# EEZ_DIB_BP3C_r2B1.net
KiCad netlist of a schematic drawn in EAGLE
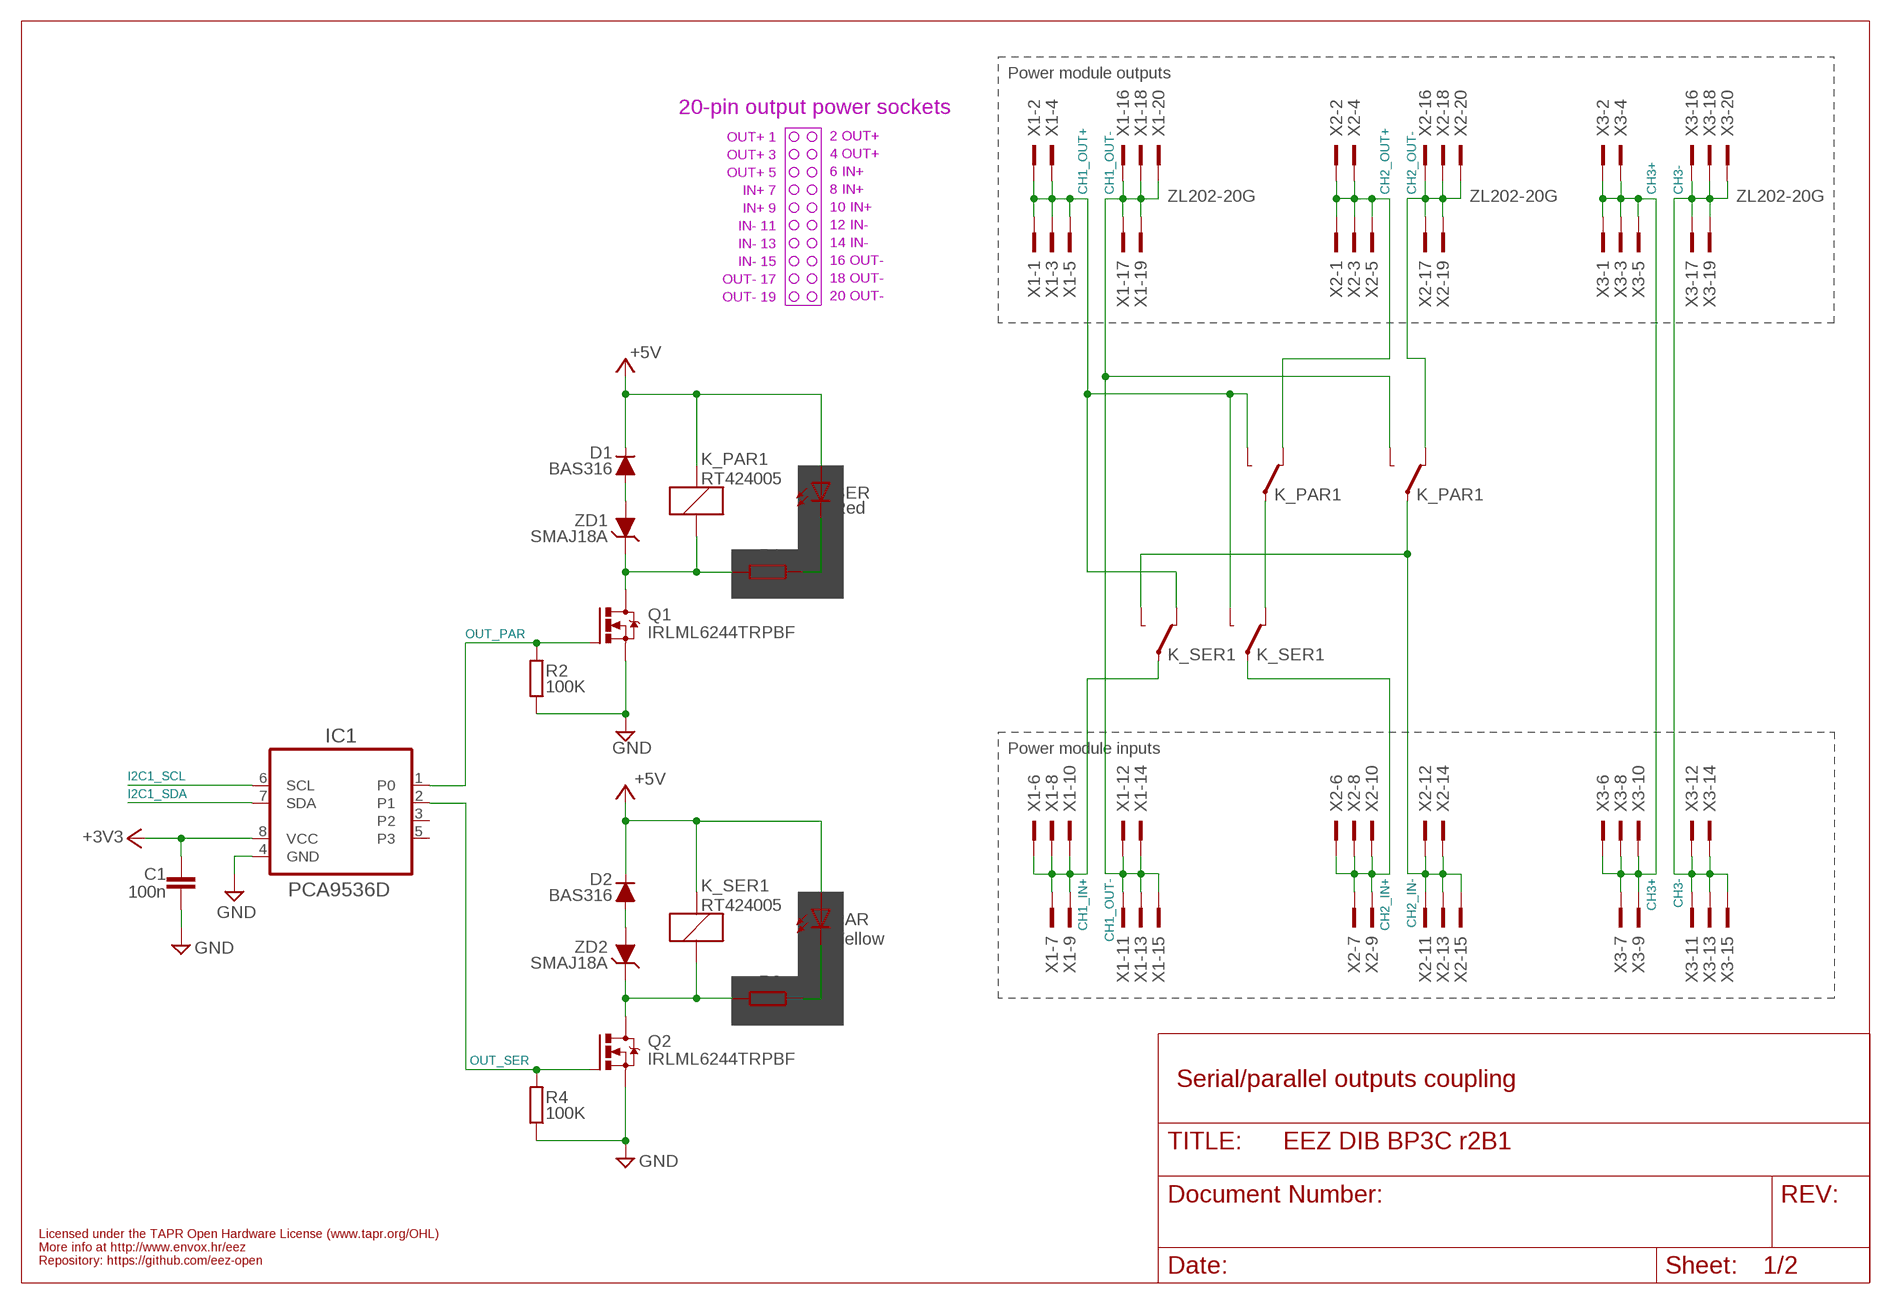
[diagram p0: schematic, sheet 1]
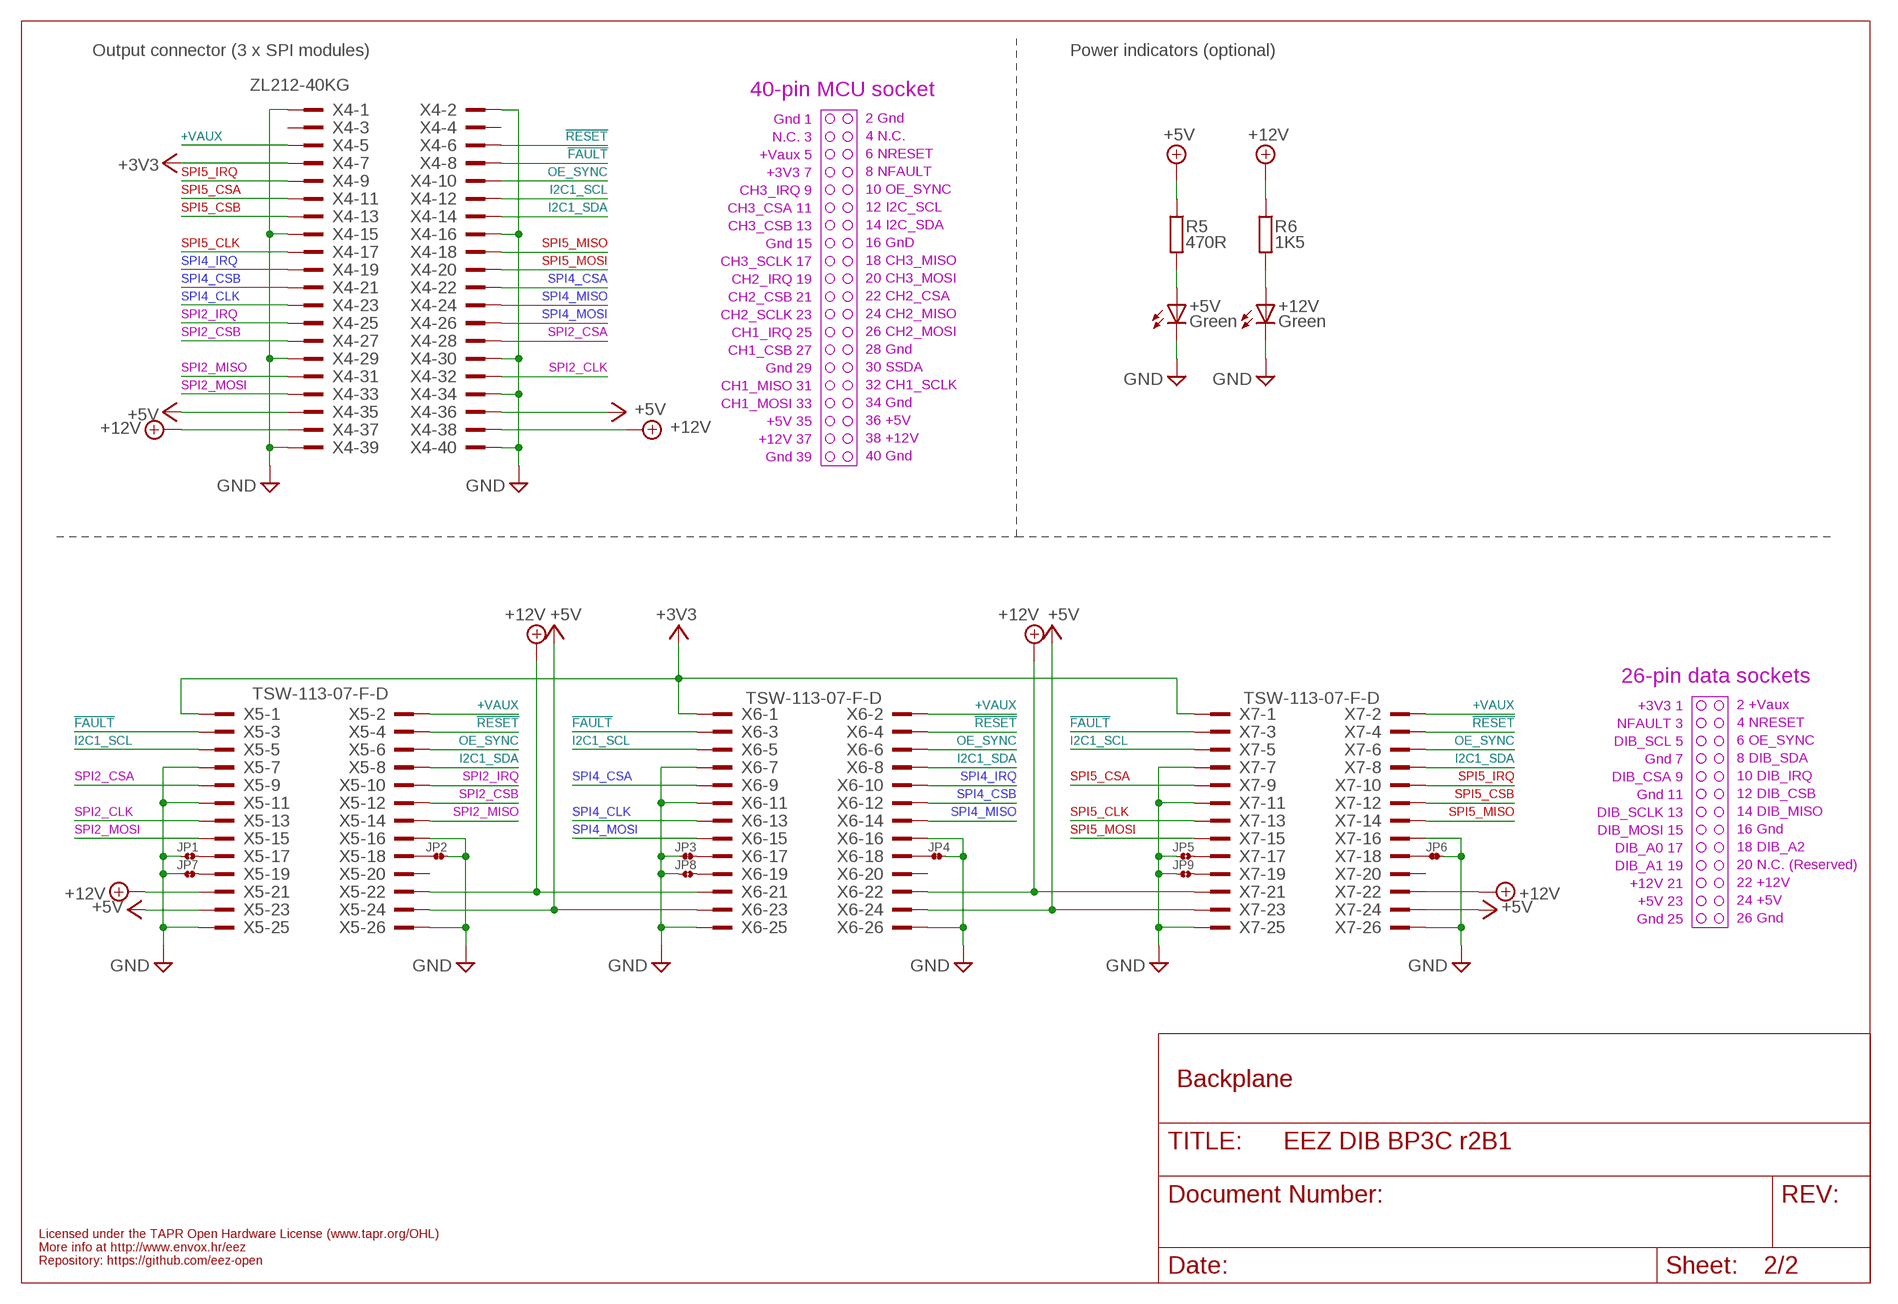
[diagram p1: schematic, sheet 2]

(export (version "E")
  (design (tool "Eeschema 10.0.6"))
  (components
    (comp (ref "C1")
      (value "100n")
      (footprint "eagle-import:C0603")
      (libsource (lib "eagle-import") (part "C-EUC0603"))
    )
    (comp (ref "D1")
      (value "BAS316")
      (footprint "eagle-import:SOD323-R")
      (libsource (lib "eagle-import") (part "DIODESOD323R"))
    )
    (comp (ref "D2")
      (value "BAS316")
      (footprint "eagle-import:SOD323-R")
      (libsource (lib "eagle-import") (part "DIODESOD323R"))
    )
    (comp (ref "IC1")
      (value "PCA9536D")
      (footprint "eagle-import:SOIC127P600X173-8N")
      (libsource (lib "eagle-import") (part "PCA9536D"))
    )
    (comp (ref "K_PAR1")
      (value "RT424005")
      (footprint "eagle-import:RT-C_016A5_ROUND")
      (libsource (lib "eagle-import") (part "RELAY_RT314012-2"))
    )
    (comp (ref "K_SER1")
      (value "RT424005")
      (footprint "eagle-import:RT-C_016A5_ROUND")
      (libsource (lib "eagle-import") (part "RELAY_RT314012-2"))
    )
    (comp (ref "PAR")
      (value "Yellow")
      (footprint "eagle-import:LED_0805")
      (libsource (lib "eagle-import") (part "LED0805"))
    )
    (comp (ref "Q1")
      (value "IRLML6244TRPBF")
      (footprint "eagle-import:SOT103P240X110-3N")
      (fields
        (field (name "MPN") "2N7002-7-F")
        (field (name "MPN_1") "2N7002-7-F")
        (field (name "OC_FARNELL") "1713823")
        (field (name "OC_NEWARK") "25R5679")
        (field (name "PACKAGE") "SOT-23-3")
        (field (name "SUPPLIER") "DIODES INC.")
      )
      (libsource (lib "eagle-import") (part "2N7002"))
    )
    (comp (ref "Q2")
      (value "IRLML6244TRPBF")
      (footprint "eagle-import:SOT103P240X110-3N")
      (fields
        (field (name "MPN") "2N7002-7-F")
        (field (name "MPN_1") "2N7002-7-F")
        (field (name "OC_FARNELL") "1713823")
        (field (name "OC_NEWARK") "25R5679")
        (field (name "PACKAGE") "SOT-23-3")
        (field (name "SUPPLIER") "DIODES INC.")
      )
      (libsource (lib "eagle-import") (part "2N7002"))
    )
    (comp (ref "R1")
      (value "330R")
      (footprint "eagle-import:R0805")
      (libsource (lib "eagle-import") (part "R-EU_R0805"))
    )
    (comp (ref "R2")
      (value "100K")
      (footprint "eagle-import:R0805")
      (libsource (lib "eagle-import") (part "R-EU_R0805"))
    )
    (comp (ref "R3")
      (value "330R")
      (footprint "eagle-import:R0805")
      (libsource (lib "eagle-import") (part "R-EU_R0805"))
    )
    (comp (ref "R4")
      (value "100K")
      (footprint "eagle-import:R0805")
      (libsource (lib "eagle-import") (part "R-EU_R0805"))
    )
    (comp (ref "SER")
      (value "Red")
      (footprint "eagle-import:LED_0805")
      (libsource (lib "eagle-import") (part "LED0805"))
    )
    (comp (ref "X1")
      (value "ZL202-20G")
      (footprint "eagle-import:DS1021-2_10SF11")
      (libsource (lib "eagle-import") (part "DS1021-210SF11"))
    )
    (comp (ref "X2")
      (value "ZL202-20G")
      (footprint "eagle-import:DS1021-2_10SF11")
      (libsource (lib "eagle-import") (part "DS1021-210SF11"))
    )
    (comp (ref "X3")
      (value "ZL202-20G")
      (footprint "eagle-import:DS1021-2_10SF11")
      (libsource (lib "eagle-import") (part "DS1021-210SF11"))
    )
    (comp (ref "ZD1")
      (value "SMAJ18A")
      (footprint "eagle-import:DO214AC")
      (libsource (lib "eagle-import") (part "PSMAXX"))
    )
    (comp (ref "ZD2")
      (value "SMAJ18A")
      (footprint "eagle-import:DO214AC")
      (libsource (lib "eagle-import") (part "PSMAXX"))
    )
    (comp (ref "+5V")
      (value "Green")
      (footprint "eagle-import:LED_0805")
      (libsource (lib "eagle-import") (part "LED0805"))
    )
    (comp (ref "+12V")
      (value "Green")
      (footprint "eagle-import:LED_0805")
      (libsource (lib "eagle-import") (part "LED0805"))
    )
    (comp (ref "JP1")
      (value "JP2-CUT")
      (footprint "eagle-import:JP2-CUT")
      (libsource (lib "eagle-import") (part "JP2-CUT"))
    )
    (comp (ref "JP2")
      (value "JP2-NOCUT")
      (footprint "eagle-import:JP2-NOCUT")
      (libsource (lib "eagle-import") (part "JP2-NOCUT"))
    )
    (comp (ref "JP3")
      (value "JP2-NOCUT")
      (footprint "eagle-import:JP2-NOCUT")
      (libsource (lib "eagle-import") (part "JP2-NOCUT"))
    )
    (comp (ref "JP4")
      (value "JP2-NOCUT")
      (footprint "eagle-import:JP2-NOCUT")
      (libsource (lib "eagle-import") (part "JP2-NOCUT"))
    )
    (comp (ref "JP5")
      (value "JP2-CUT")
      (footprint "eagle-import:JP2-CUT")
      (libsource (lib "eagle-import") (part "JP2-CUT"))
    )
    (comp (ref "JP6")
      (value "JP2-NOCUT")
      (footprint "eagle-import:JP2-NOCUT")
      (libsource (lib "eagle-import") (part "JP2-NOCUT"))
    )
    (comp (ref "JP7")
      (value "JP2-NOCUT")
      (footprint "eagle-import:JP2-NOCUT")
      (libsource (lib "eagle-import") (part "JP2-NOCUT"))
    )
    (comp (ref "JP8")
      (value "JP2-CUT")
      (footprint "eagle-import:JP2-CUT")
      (libsource (lib "eagle-import") (part "JP2-CUT"))
    )
    (comp (ref "JP9")
      (value "JP2-CUT")
      (footprint "eagle-import:JP2-CUT")
      (libsource (lib "eagle-import") (part "JP2-CUT"))
    )
    (comp (ref "R5")
      (value "470R")
      (footprint "eagle-import:R0805")
      (libsource (lib "eagle-import") (part "R-EU_R0805"))
    )
    (comp (ref "R6")
      (value "1K5")
      (footprint "eagle-import:R0805")
      (libsource (lib "eagle-import") (part "R-EU_R0805"))
    )
    (comp (ref "X4")
      (value "ZL212-40KG")
      (footprint "eagle-import:ZL212-40KG")
      (libsource (lib "eagle-import") (part "ZL212-40KG"))
    )
    (comp (ref "X5")
      (value "TSW-113-07-F-D")
      (footprint "eagle-import:TSW-113-07-F-D")
      (libsource (lib "eagle-import") (part "TSW-113-07-F-D"))
    )
    (comp (ref "X6")
      (value "TSW-113-07-F-D")
      (footprint "eagle-import:TSW-113-07-F-D")
      (libsource (lib "eagle-import") (part "TSW-113-07-F-D"))
    )
    (comp (ref "X7")
      (value "TSW-113-07-F-D")
      (footprint "eagle-import:TSW-113-07-F-D")
      (libsource (lib "eagle-import") (part "TSW-113-07-F-D"))
    )
  )
  (nets
    (net (code "1") (name "+3V3") (class "Default")
      (node (ref "C1") (pin "1") (pinfunction "1_1") (pintype "passive"))
      (node (ref "IC1") (pin "8") (pinfunction "VCC_8") (pintype "passive"))
      (node (ref "X4") (pin "7") (pinfunction "1_7") (pintype "passive"))
      (node (ref "X5") (pin "1") (pinfunction "1_1") (pintype "passive"))
      (node (ref "X6") (pin "1") (pinfunction "1_1") (pintype "passive"))
      (node (ref "X7") (pin "1") (pinfunction "1_1") (pintype "passive"))
    )
    (net (code "2") (name "+5V") (class "Default")
      (node (ref "D1") (pin "C") (pinfunction "C_C") (pintype "passive"))
      (node (ref "D2") (pin "C") (pinfunction "C_C") (pintype "passive"))
      (node (ref "K_PAR1") (pin "A2") (pinfunction "C1_A2") (pintype "passive"))
      (node (ref "K_SER1") (pin "A2") (pinfunction "C1_A2") (pintype "passive"))
      (node (ref "PAR") (pin "A") (pinfunction "A_A") (pintype "passive"))
      (node (ref "R5") (pin "1") (pinfunction "1_1") (pintype "passive"))
      (node (ref "SER") (pin "A") (pinfunction "A_A") (pintype "passive"))
      (node (ref "X4") (pin "35") (pinfunction "1_35") (pintype "passive"))
      (node (ref "X4") (pin "36") (pinfunction "1_36") (pintype "passive"))
      (node (ref "X5") (pin "23") (pinfunction "1_23") (pintype "passive"))
      (node (ref "X5") (pin "24") (pinfunction "1_24") (pintype "passive"))
      (node (ref "X6") (pin "23") (pinfunction "1_23") (pintype "passive"))
      (node (ref "X6") (pin "24") (pinfunction "1_24") (pintype "passive"))
      (node (ref "X7") (pin "23") (pinfunction "1_23") (pintype "passive"))
      (node (ref "X7") (pin "24") (pinfunction "1_24") (pintype "passive"))
    )
    (net (code "3") (name "+12V") (class "Default")
      (node (ref "R6") (pin "1") (pinfunction "1_1") (pintype "passive"))
      (node (ref "X4") (pin "37") (pinfunction "1_37") (pintype "passive"))
      (node (ref "X4") (pin "38") (pinfunction "1_38") (pintype "passive"))
      (node (ref "X5") (pin "21") (pinfunction "1_21") (pintype "passive"))
      (node (ref "X5") (pin "22") (pinfunction "1_22") (pintype "passive"))
      (node (ref "X6") (pin "21") (pinfunction "1_21") (pintype "passive"))
      (node (ref "X6") (pin "22") (pinfunction "1_22") (pintype "passive"))
      (node (ref "X7") (pin "21") (pinfunction "1_21") (pintype "passive"))
      (node (ref "X7") (pin "22") (pinfunction "1_22") (pintype "passive"))
    )
    (net (code "4") (name "+VAUX") (class "Default")
      (node (ref "X4") (pin "5") (pinfunction "1_5") (pintype "passive"))
      (node (ref "X5") (pin "2") (pinfunction "1_2") (pintype "passive"))
      (node (ref "X6") (pin "2") (pinfunction "1_2") (pintype "passive"))
      (node (ref "X7") (pin "2") (pinfunction "1_2") (pintype "passive"))
    )
    (net (code "5") (name "CH1_IN+") (class "Default")
      (node (ref "K_SER1") (pin "11A") (pinfunction "P_11A") (pintype "passive"))
      (node (ref "X1") (pin "10") (pinfunction "1_10") (pintype "passive"))
      (node (ref "X1") (pin "6") (pinfunction "1_6") (pintype "passive"))
      (node (ref "X1") (pin "7") (pinfunction "1_7") (pintype "passive"))
      (node (ref "X1") (pin "8") (pinfunction "1_8") (pintype "passive"))
      (node (ref "X1") (pin "9") (pinfunction "1_9") (pintype "passive"))
    )
    (net (code "6") (name "CH1_OUT+") (class "Default")
      (node (ref "K_PAR1") (pin "14A") (pinfunction "O_14A") (pintype "passive"))
      (node (ref "K_SER1") (pin "12A") (pinfunction "S_12A") (pintype "passive"))
      (node (ref "K_SER1") (pin "14B") (pinfunction "O_14B") (pintype "passive"))
      (node (ref "X1") (pin "1") (pinfunction "1_1") (pintype "passive"))
      (node (ref "X1") (pin "2") (pinfunction "1_2") (pintype "passive"))
      (node (ref "X1") (pin "3") (pinfunction "1_3") (pintype "passive"))
      (node (ref "X1") (pin "4") (pinfunction "1_4") (pintype "passive"))
      (node (ref "X1") (pin "5") (pinfunction "1_5") (pintype "passive"))
    )
    (net (code "7") (name "CH1_OUT-") (class "Default")
      (node (ref "K_PAR1") (pin "14B") (pinfunction "O_14B") (pintype "passive"))
      (node (ref "X1") (pin "11") (pinfunction "1_11") (pintype "passive"))
      (node (ref "X1") (pin "12") (pinfunction "1_12") (pintype "passive"))
      (node (ref "X1") (pin "13") (pinfunction "1_13") (pintype "passive"))
      (node (ref "X1") (pin "14") (pinfunction "1_14") (pintype "passive"))
      (node (ref "X1") (pin "15") (pinfunction "1_15") (pintype "passive"))
      (node (ref "X1") (pin "16") (pinfunction "1_16") (pintype "passive"))
      (node (ref "X1") (pin "17") (pinfunction "1_17") (pintype "passive"))
      (node (ref "X1") (pin "18") (pinfunction "1_18") (pintype "passive"))
      (node (ref "X1") (pin "19") (pinfunction "1_19") (pintype "passive"))
      (node (ref "X1") (pin "20") (pinfunction "1_20") (pintype "passive"))
    )
    (net (code "8") (name "CH2_IN+") (class "Default")
      (node (ref "K_SER1") (pin "11B") (pinfunction "P_11B") (pintype "passive"))
      (node (ref "X2") (pin "10") (pinfunction "1_10") (pintype "passive"))
      (node (ref "X2") (pin "6") (pinfunction "1_6") (pintype "passive"))
      (node (ref "X2") (pin "7") (pinfunction "1_7") (pintype "passive"))
      (node (ref "X2") (pin "8") (pinfunction "1_8") (pintype "passive"))
      (node (ref "X2") (pin "9") (pinfunction "1_9") (pintype "passive"))
    )
    (net (code "9") (name "CH2_IN-") (class "Default")
      (node (ref "K_PAR1") (pin "11B") (pinfunction "P_11B") (pintype "passive"))
      (node (ref "K_SER1") (pin "14A") (pinfunction "O_14A") (pintype "passive"))
      (node (ref "X2") (pin "11") (pinfunction "1_11") (pintype "passive"))
      (node (ref "X2") (pin "12") (pinfunction "1_12") (pintype "passive"))
      (node (ref "X2") (pin "13") (pinfunction "1_13") (pintype "passive"))
      (node (ref "X2") (pin "14") (pinfunction "1_14") (pintype "passive"))
      (node (ref "X2") (pin "15") (pinfunction "1_15") (pintype "passive"))
    )
    (net (code "10") (name "CH2_OUT+") (class "Default")
      (node (ref "K_PAR1") (pin "12A") (pinfunction "S_12A") (pintype "passive"))
      (node (ref "X2") (pin "1") (pinfunction "1_1") (pintype "passive"))
      (node (ref "X2") (pin "2") (pinfunction "1_2") (pintype "passive"))
      (node (ref "X2") (pin "3") (pinfunction "1_3") (pintype "passive"))
      (node (ref "X2") (pin "4") (pinfunction "1_4") (pintype "passive"))
      (node (ref "X2") (pin "5") (pinfunction "1_5") (pintype "passive"))
    )
    (net (code "11") (name "CH2_OUT-") (class "Default")
      (node (ref "K_PAR1") (pin "12B") (pinfunction "S_12B") (pintype "passive"))
      (node (ref "X2") (pin "16") (pinfunction "1_16") (pintype "passive"))
      (node (ref "X2") (pin "17") (pinfunction "1_17") (pintype "passive"))
      (node (ref "X2") (pin "18") (pinfunction "1_18") (pintype "passive"))
      (node (ref "X2") (pin "19") (pinfunction "1_19") (pintype "passive"))
      (node (ref "X2") (pin "20") (pinfunction "1_20") (pintype "passive"))
    )
    (net (code "12") (name "CH3+") (class "Default")
      (node (ref "X3") (pin "1") (pinfunction "1_1") (pintype "passive"))
      (node (ref "X3") (pin "10") (pinfunction "1_10") (pintype "passive"))
      (node (ref "X3") (pin "2") (pinfunction "1_2") (pintype "passive"))
      (node (ref "X3") (pin "3") (pinfunction "1_3") (pintype "passive"))
      (node (ref "X3") (pin "4") (pinfunction "1_4") (pintype "passive"))
      (node (ref "X3") (pin "5") (pinfunction "1_5") (pintype "passive"))
      (node (ref "X3") (pin "6") (pinfunction "1_6") (pintype "passive"))
      (node (ref "X3") (pin "7") (pinfunction "1_7") (pintype "passive"))
      (node (ref "X3") (pin "8") (pinfunction "1_8") (pintype "passive"))
      (node (ref "X3") (pin "9") (pinfunction "1_9") (pintype "passive"))
    )
    (net (code "13") (name "CH3-") (class "Default")
      (node (ref "X3") (pin "11") (pinfunction "1_11") (pintype "passive"))
      (node (ref "X3") (pin "12") (pinfunction "1_12") (pintype "passive"))
      (node (ref "X3") (pin "13") (pinfunction "1_13") (pintype "passive"))
      (node (ref "X3") (pin "14") (pinfunction "1_14") (pintype "passive"))
      (node (ref "X3") (pin "15") (pinfunction "1_15") (pintype "passive"))
      (node (ref "X3") (pin "16") (pinfunction "1_16") (pintype "passive"))
      (node (ref "X3") (pin "17") (pinfunction "1_17") (pintype "passive"))
      (node (ref "X3") (pin "18") (pinfunction "1_18") (pintype "passive"))
      (node (ref "X3") (pin "19") (pinfunction "1_19") (pintype "passive"))
      (node (ref "X3") (pin "20") (pinfunction "1_20") (pintype "passive"))
    )
    (net (code "14") (name "GND") (class "Default")
      (node (ref "+12V") (pin "C") (pinfunction "C_C") (pintype "passive"))
      (node (ref "+5V") (pin "C") (pinfunction "C_C") (pintype "passive"))
      (node (ref "C1") (pin "2") (pinfunction "2_2") (pintype "passive"))
      (node (ref "IC1") (pin "4") (pinfunction "GND_4") (pintype "passive"))
      (node (ref "JP1") (pin "1") (pinfunction "1_1") (pintype "passive"))
      (node (ref "JP2") (pin "2") (pinfunction "2_2") (pintype "passive"))
      (node (ref "JP3") (pin "1") (pinfunction "1_1") (pintype "passive"))
      (node (ref "JP4") (pin "2") (pinfunction "2_2") (pintype "passive"))
      (node (ref "JP5") (pin "1") (pinfunction "1_1") (pintype "passive"))
      (node (ref "JP6") (pin "2") (pinfunction "2_2") (pintype "passive"))
      (node (ref "JP7") (pin "1") (pinfunction "1_1") (pintype "passive"))
      (node (ref "JP8") (pin "1") (pinfunction "1_1") (pintype "passive"))
      (node (ref "JP9") (pin "1") (pinfunction "1_1") (pintype "passive"))
      (node (ref "Q1") (pin "2") (pinfunction "S_2") (pintype "passive"))
      (node (ref "Q2") (pin "2") (pinfunction "S_2") (pintype "passive"))
      (node (ref "R2") (pin "1") (pinfunction "1_1") (pintype "passive"))
      (node (ref "R4") (pin "1") (pinfunction "1_1") (pintype "passive"))
      (node (ref "X4") (pin "1") (pinfunction "1_1") (pintype "passive"))
      (node (ref "X4") (pin "15") (pinfunction "1_15") (pintype "passive"))
      (node (ref "X4") (pin "16") (pinfunction "1_16") (pintype "passive"))
      (node (ref "X4") (pin "2") (pinfunction "1_2") (pintype "passive"))
      (node (ref "X4") (pin "29") (pinfunction "1_29") (pintype "passive"))
      (node (ref "X4") (pin "30") (pinfunction "1_30") (pintype "passive"))
      (node (ref "X4") (pin "34") (pinfunction "1_34") (pintype "passive"))
      (node (ref "X4") (pin "39") (pinfunction "1_39") (pintype "passive"))
      (node (ref "X4") (pin "40") (pinfunction "1_40") (pintype "passive"))
      (node (ref "X5") (pin "11") (pinfunction "1_11") (pintype "passive"))
      (node (ref "X5") (pin "16") (pinfunction "1_16") (pintype "passive"))
      (node (ref "X5") (pin "25") (pinfunction "1_25") (pintype "passive"))
      (node (ref "X5") (pin "26") (pinfunction "1_26") (pintype "passive"))
      (node (ref "X5") (pin "7") (pinfunction "1_7") (pintype "passive"))
      (node (ref "X6") (pin "11") (pinfunction "1_11") (pintype "passive"))
      (node (ref "X6") (pin "16") (pinfunction "1_16") (pintype "passive"))
      (node (ref "X6") (pin "25") (pinfunction "1_25") (pintype "passive"))
      (node (ref "X6") (pin "26") (pinfunction "1_26") (pintype "passive"))
      (node (ref "X6") (pin "7") (pinfunction "1_7") (pintype "passive"))
      (node (ref "X7") (pin "11") (pinfunction "1_11") (pintype "passive"))
      (node (ref "X7") (pin "16") (pinfunction "1_16") (pintype "passive"))
      (node (ref "X7") (pin "25") (pinfunction "1_25") (pintype "passive"))
      (node (ref "X7") (pin "26") (pinfunction "1_26") (pintype "passive"))
      (node (ref "X7") (pin "7") (pinfunction "1_7") (pintype "passive"))
    )
    (net (code "15") (name "I2C1_SCL") (class "Default")
      (node (ref "IC1") (pin "6") (pinfunction "SCL_6") (pintype "input"))
      (node (ref "X4") (pin "12") (pinfunction "1_12") (pintype "passive"))
      (node (ref "X5") (pin "5") (pinfunction "1_5") (pintype "passive"))
      (node (ref "X6") (pin "5") (pinfunction "1_5") (pintype "passive"))
      (node (ref "X7") (pin "5") (pinfunction "1_5") (pintype "passive"))
    )
    (net (code "16") (name "I2C1_SDA") (class "Default")
      (node (ref "IC1") (pin "7") (pinfunction "SDA_7") (pintype "bidirectional"))
      (node (ref "X4") (pin "14") (pinfunction "1_14") (pintype "passive"))
      (node (ref "X5") (pin "8") (pinfunction "1_8") (pintype "passive"))
      (node (ref "X6") (pin "8") (pinfunction "1_8") (pintype "passive"))
      (node (ref "X7") (pin "8") (pinfunction "1_8") (pintype "passive"))
    )
    (net (code "17") (name "Net-(+5V-PadA)") (class "Default")
      (node (ref "+5V") (pin "A") (pinfunction "A_A") (pintype "passive"))
      (node (ref "R5") (pin "2") (pinfunction "2_2") (pintype "passive"))
    )
    (net (code "18") (name "Net-(+12V-PadA)") (class "Default")
      (node (ref "+12V") (pin "A") (pinfunction "A_A") (pintype "passive"))
      (node (ref "R6") (pin "2") (pinfunction "2_2") (pintype "passive"))
    )
    (net (code "19") (name "Net-(D1-PadA)") (class "Default")
      (node (ref "D1") (pin "A") (pinfunction "A_A") (pintype "passive"))
      (node (ref "ZD1") (pin "A") (pinfunction "A_A") (pintype "passive"))
    )
    (net (code "20") (name "Net-(D2-PadA)") (class "Default")
      (node (ref "D2") (pin "A") (pinfunction "A_A") (pintype "passive"))
      (node (ref "ZD2") (pin "A") (pinfunction "A_A") (pintype "passive"))
    )
    (net (code "21") (name "Net-(K_PAR1A-P)") (class "Default")
      (node (ref "K_PAR1") (pin "11A") (pinfunction "P_11A") (pintype "passive"))
      (node (ref "K_SER1") (pin "12B") (pinfunction "S_12B") (pintype "passive"))
    )
    (net (code "22") (name "Net-(K_PAR1C-C2)") (class "Default")
      (node (ref "K_PAR1") (pin "A1") (pinfunction "C2_A1") (pintype "passive"))
      (node (ref "Q1") (pin "3") (pinfunction "D_3") (pintype "passive"))
      (node (ref "R1") (pin "2") (pinfunction "2_2") (pintype "passive"))
      (node (ref "ZD1") (pin "C") (pinfunction "C_C") (pintype "passive"))
    )
    (net (code "23") (name "Net-(K_SER1C-C2)") (class "Default")
      (node (ref "K_SER1") (pin "A1") (pinfunction "C2_A1") (pintype "passive"))
      (node (ref "Q2") (pin "3") (pinfunction "D_3") (pintype "passive"))
      (node (ref "R3") (pin "2") (pinfunction "2_2") (pintype "passive"))
      (node (ref "ZD2") (pin "C") (pinfunction "C_C") (pintype "passive"))
    )
    (net (code "24") (name "Net-(PAR-PadC)") (class "Default")
      (node (ref "PAR") (pin "C") (pinfunction "C_C") (pintype "passive"))
      (node (ref "R3") (pin "1") (pinfunction "1_1") (pintype "passive"))
    )
    (net (code "25") (name "Net-(R1-Pad1)") (class "Default")
      (node (ref "R1") (pin "1") (pinfunction "1_1") (pintype "passive"))
      (node (ref "SER") (pin "C") (pinfunction "C_C") (pintype "passive"))
    )
    (net (code "26") (name "Net-(X5I-1)") (class "Default")
      (node (ref "JP1") (pin "2") (pinfunction "2_2") (pintype "passive"))
      (node (ref "X5") (pin "17") (pinfunction "1_17") (pintype "passive"))
    )
    (net (code "27") (name "Net-(X5J-1)") (class "Default")
      (node (ref "JP2") (pin "1") (pinfunction "1_1") (pintype "passive"))
      (node (ref "X5") (pin "18") (pinfunction "1_18") (pintype "passive"))
    )
    (net (code "28") (name "Net-(X5K-1)") (class "Default")
      (node (ref "JP7") (pin "2") (pinfunction "2_2") (pintype "passive"))
      (node (ref "X5") (pin "19") (pinfunction "1_19") (pintype "passive"))
    )
    (net (code "29") (name "Net-(X6I-1)") (class "Default")
      (node (ref "JP3") (pin "2") (pinfunction "2_2") (pintype "passive"))
      (node (ref "X6") (pin "17") (pinfunction "1_17") (pintype "passive"))
    )
    (net (code "30") (name "Net-(X6J-1)") (class "Default")
      (node (ref "JP4") (pin "1") (pinfunction "1_1") (pintype "passive"))
      (node (ref "X6") (pin "18") (pinfunction "1_18") (pintype "passive"))
    )
    (net (code "31") (name "Net-(X6K-1)") (class "Default")
      (node (ref "JP8") (pin "2") (pinfunction "2_2") (pintype "passive"))
      (node (ref "X6") (pin "19") (pinfunction "1_19") (pintype "passive"))
    )
    (net (code "32") (name "Net-(X7I-1)") (class "Default")
      (node (ref "JP5") (pin "2") (pinfunction "2_2") (pintype "passive"))
      (node (ref "X7") (pin "17") (pinfunction "1_17") (pintype "passive"))
    )
    (net (code "33") (name "Net-(X7J-1)") (class "Default")
      (node (ref "JP6") (pin "1") (pinfunction "1_1") (pintype "passive"))
      (node (ref "X7") (pin "18") (pinfunction "1_18") (pintype "passive"))
    )
    (net (code "34") (name "Net-(X7K-1)") (class "Default")
      (node (ref "JP9") (pin "2") (pinfunction "2_2") (pintype "passive"))
      (node (ref "X7") (pin "19") (pinfunction "1_19") (pintype "passive"))
    )
    (net (code "35") (name "OE_SYNC") (class "Default")
      (node (ref "X4") (pin "10") (pinfunction "1_10") (pintype "passive"))
      (node (ref "X5") (pin "6") (pinfunction "1_6") (pintype "passive"))
      (node (ref "X6") (pin "6") (pinfunction "1_6") (pintype "passive"))
      (node (ref "X7") (pin "6") (pinfunction "1_6") (pintype "passive"))
    )
    (net (code "36") (name "OUT_PAR") (class "Default")
      (node (ref "IC1") (pin "1") (pinfunction "P0_1") (pintype "bidirectional"))
      (node (ref "Q1") (pin "1") (pinfunction "G_1") (pintype "passive"))
      (node (ref "R2") (pin "2") (pinfunction "2_2") (pintype "passive"))
    )
    (net (code "37") (name "OUT_SER") (class "Default")
      (node (ref "IC1") (pin "2") (pinfunction "P1_2") (pintype "bidirectional"))
      (node (ref "Q2") (pin "1") (pinfunction "G_1") (pintype "passive"))
      (node (ref "R4") (pin "2") (pinfunction "2_2") (pintype "passive"))
    )
    (net (code "38") (name "SPI2_CLK") (class "Default")
      (node (ref "X4") (pin "32") (pinfunction "1_32") (pintype "passive"))
      (node (ref "X5") (pin "13") (pinfunction "1_13") (pintype "passive"))
    )
    (net (code "39") (name "SPI2_CSA") (class "Default")
      (node (ref "X4") (pin "28") (pinfunction "1_28") (pintype "passive"))
      (node (ref "X5") (pin "9") (pinfunction "1_9") (pintype "passive"))
    )
    (net (code "40") (name "SPI2_CSB") (class "Default")
      (node (ref "X4") (pin "27") (pinfunction "1_27") (pintype "passive"))
      (node (ref "X5") (pin "12") (pinfunction "1_12") (pintype "passive"))
    )
    (net (code "41") (name "SPI2_IRQ") (class "Default")
      (node (ref "X4") (pin "25") (pinfunction "1_25") (pintype "passive"))
      (node (ref "X5") (pin "10") (pinfunction "1_10") (pintype "passive"))
    )
    (net (code "42") (name "SPI2_MISO") (class "Default")
      (node (ref "X4") (pin "31") (pinfunction "1_31") (pintype "passive"))
      (node (ref "X5") (pin "14") (pinfunction "1_14") (pintype "passive"))
    )
    (net (code "43") (name "SPI2_MOSI") (class "Default")
      (node (ref "X4") (pin "33") (pinfunction "1_33") (pintype "passive"))
      (node (ref "X5") (pin "15") (pinfunction "1_15") (pintype "passive"))
    )
    (net (code "44") (name "SPI4_CLK") (class "Default")
      (node (ref "X4") (pin "23") (pinfunction "1_23") (pintype "passive"))
      (node (ref "X6") (pin "13") (pinfunction "1_13") (pintype "passive"))
    )
    (net (code "45") (name "SPI4_CSA") (class "Default")
      (node (ref "X4") (pin "22") (pinfunction "1_22") (pintype "passive"))
      (node (ref "X6") (pin "9") (pinfunction "1_9") (pintype "passive"))
    )
    (net (code "46") (name "SPI4_CSB") (class "Default")
      (node (ref "X4") (pin "21") (pinfunction "1_21") (pintype "passive"))
      (node (ref "X6") (pin "12") (pinfunction "1_12") (pintype "passive"))
    )
    (net (code "47") (name "SPI4_IRQ") (class "Default")
      (node (ref "X4") (pin "19") (pinfunction "1_19") (pintype "passive"))
      (node (ref "X6") (pin "10") (pinfunction "1_10") (pintype "passive"))
    )
    (net (code "48") (name "SPI4_MISO") (class "Default")
      (node (ref "X4") (pin "24") (pinfunction "1_24") (pintype "passive"))
      (node (ref "X6") (pin "14") (pinfunction "1_14") (pintype "passive"))
    )
    (net (code "49") (name "SPI4_MOSI") (class "Default")
      (node (ref "X4") (pin "26") (pinfunction "1_26") (pintype "passive"))
      (node (ref "X6") (pin "15") (pinfunction "1_15") (pintype "passive"))
    )
    (net (code "50") (name "SPI5_CLK") (class "Default")
      (node (ref "X4") (pin "17") (pinfunction "1_17") (pintype "passive"))
      (node (ref "X7") (pin "13") (pinfunction "1_13") (pintype "passive"))
    )
    (net (code "51") (name "SPI5_CSA") (class "Default")
      (node (ref "X4") (pin "11") (pinfunction "1_11") (pintype "passive"))
      (node (ref "X7") (pin "9") (pinfunction "1_9") (pintype "passive"))
    )
    (net (code "52") (name "SPI5_CSB") (class "Default")
      (node (ref "X4") (pin "13") (pinfunction "1_13") (pintype "passive"))
      (node (ref "X7") (pin "12") (pinfunction "1_12") (pintype "passive"))
    )
    (net (code "53") (name "SPI5_IRQ") (class "Default")
      (node (ref "X4") (pin "9") (pinfunction "1_9") (pintype "passive"))
      (node (ref "X7") (pin "10") (pinfunction "1_10") (pintype "passive"))
    )
    (net (code "54") (name "SPI5_MISO") (class "Default")
      (node (ref "X4") (pin "18") (pinfunction "1_18") (pintype "passive"))
      (node (ref "X7") (pin "14") (pinfunction "1_14") (pintype "passive"))
    )
    (net (code "55") (name "SPI5_MOSI") (class "Default")
      (node (ref "X4") (pin "20") (pinfunction "1_20") (pintype "passive"))
      (node (ref "X7") (pin "15") (pinfunction "1_15") (pintype "passive"))
    )
    (net (code "56") (name "unconnected-(IC1-P2-Pad3)") (class "Default")
      (node (ref "IC1") (pin "3") (pinfunction "P2_3") (pintype "bidirectional"))
    )
    (net (code "57") (name "unconnected-(IC1-P3-Pad5)") (class "Default")
      (node (ref "IC1") (pin "5") (pinfunction "P3_5") (pintype "bidirectional"))
    )
    (net (code "58") (name "unconnected-(X4AH-1-Pad4)") (class "Default")
      (node (ref "X4") (pin "4") (pinfunction "1_4") (pintype "passive"))
    )
    (net (code "59") (name "unconnected-(X4W-1-Pad3)") (class "Default")
      (node (ref "X4") (pin "3") (pinfunction "1_3") (pintype "passive"))
    )
    (net (code "60") (name "unconnected-(X5M-1-Pad20)") (class "Default")
      (node (ref "X5") (pin "20") (pinfunction "1_20") (pintype "passive"))
    )
    (net (code "61") (name "unconnected-(X6M-1-Pad20)") (class "Default")
      (node (ref "X6") (pin "20") (pinfunction "1_20") (pintype "passive"))
    )
    (net (code "62") (name "unconnected-(X7M-1-Pad20)") (class "Default")
      (node (ref "X7") (pin "20") (pinfunction "1_20") (pintype "passive"))
    )
    (net (code "63") (name "~{FAULT}") (class "Default")
      (node (ref "X4") (pin "8") (pinfunction "1_8") (pintype "passive"))
      (node (ref "X5") (pin "3") (pinfunction "1_3") (pintype "passive"))
      (node (ref "X6") (pin "3") (pinfunction "1_3") (pintype "passive"))
      (node (ref "X7") (pin "3") (pinfunction "1_3") (pintype "passive"))
    )
    (net (code "64") (name "~{RESET}") (class "Default")
      (node (ref "X4") (pin "6") (pinfunction "1_6") (pintype "passive"))
      (node (ref "X5") (pin "4") (pinfunction "1_4") (pintype "passive"))
      (node (ref "X6") (pin "4") (pinfunction "1_4") (pintype "passive"))
      (node (ref "X7") (pin "4") (pinfunction "1_4") (pintype "passive"))
    )
  )
)
